# Reg.net
KiCad netlist of a schematic drawn in EAGLE
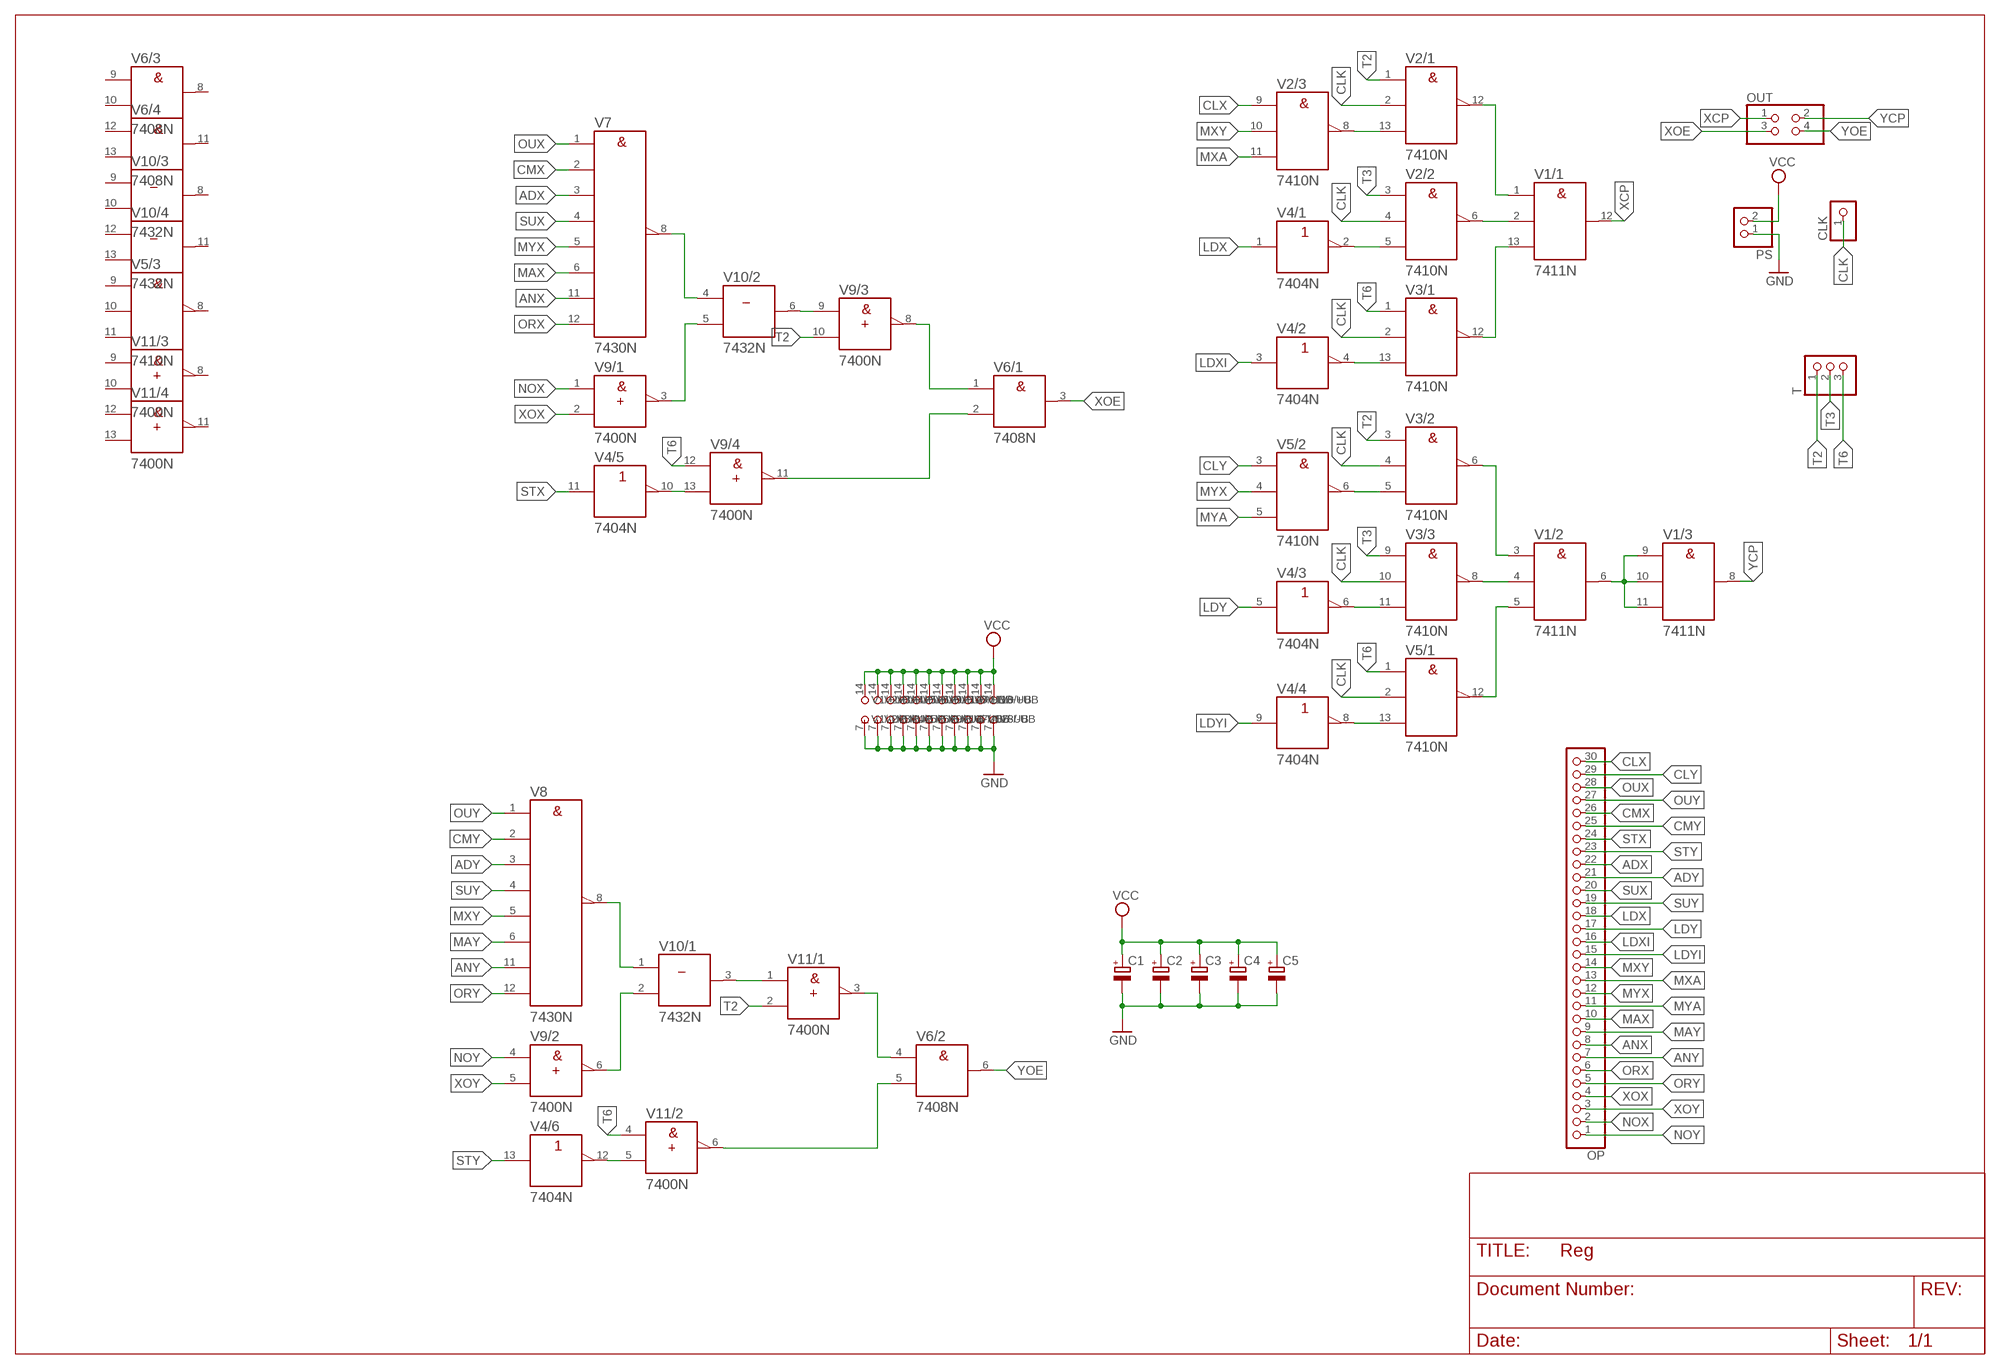
[diagram p0: schematic, sheet 1]

(export (version "E")
  (design (tool "Eeschema 10.0.6"))
  (components
    (comp (ref "C1")
      (value "CPOL-EUE2-5")
      (footprint "eagle-import:E2-5")
      (libsource (lib "eagle-import") (part "CPOL-EUE2-5"))
    )
    (comp (ref "C2")
      (value "CPOL-EUE2-5")
      (footprint "eagle-import:E2-5")
      (libsource (lib "eagle-import") (part "CPOL-EUE2-5"))
    )
    (comp (ref "C3")
      (value "CPOL-EUE2-5")
      (footprint "eagle-import:E2-5")
      (libsource (lib "eagle-import") (part "CPOL-EUE2-5"))
    )
    (comp (ref "C4")
      (value "CPOL-EUE2-5")
      (footprint "eagle-import:E2-5")
      (libsource (lib "eagle-import") (part "CPOL-EUE2-5"))
    )
    (comp (ref "C5")
      (value "CPOL-EUE2-5")
      (footprint "eagle-import:E2-5")
      (libsource (lib "eagle-import") (part "CPOL-EUE2-5"))
    )
    (comp (ref "CLK")
      (value "PINHD-1X1")
      (footprint "eagle-import:1X01")
      (libsource (lib "eagle-import") (part "PINHD-1X1"))
    )
    (comp (ref "OP")
      (value "PINHD-1X30")
      (footprint "eagle-import:1X30")
      (libsource (lib "eagle-import") (part "PINHD-1X30"))
    )
    (comp (ref "OUT")
      (value "PINHD-2X2")
      (footprint "eagle-import:2X02")
      (libsource (lib "eagle-import") (part "PINHD-2X2"))
    )
    (comp (ref "PS")
      (value "PINHD-1X2")
      (footprint "eagle-import:1X02")
      (libsource (lib "eagle-import") (part "PINHD-1X2"))
    )
    (comp (ref "T")
      (value "PINHD-1X3")
      (footprint "eagle-import:1X03")
      (libsource (lib "eagle-import") (part "PINHD-1X3"))
    )
    (comp (ref "V1")
      (value "7411N")
      (footprint "eagle-import:DIL14")
      (libsource (lib "eagle-import") (part "7411N"))
    )
    (comp (ref "V2")
      (value "7410N")
      (footprint "eagle-import:DIL14")
      (libsource (lib "eagle-import") (part "7410N"))
    )
    (comp (ref "V3")
      (value "7410N")
      (footprint "eagle-import:DIL14")
      (libsource (lib "eagle-import") (part "7410N"))
    )
    (comp (ref "V4")
      (value "7404N")
      (footprint "eagle-import:DIL14")
      (libsource (lib "eagle-import") (part "7404N"))
    )
    (comp (ref "V5")
      (value "7410N")
      (footprint "eagle-import:DIL14")
      (libsource (lib "eagle-import") (part "7410N"))
    )
    (comp (ref "V6")
      (value "7408N")
      (footprint "eagle-import:DIL14")
      (libsource (lib "eagle-import") (part "7408N"))
    )
    (comp (ref "V7")
      (value "7430N")
      (footprint "eagle-import:DIL14")
      (libsource (lib "eagle-import") (part "7430N"))
    )
    (comp (ref "V8")
      (value "7430N")
      (footprint "eagle-import:DIL14")
      (libsource (lib "eagle-import") (part "7430N"))
    )
    (comp (ref "V9")
      (value "7400N")
      (footprint "eagle-import:DIL14")
      (libsource (lib "eagle-import") (part "7400N"))
    )
    (comp (ref "V10")
      (value "7432N")
      (footprint "eagle-import:DIL14")
      (libsource (lib "eagle-import") (part "7432N"))
    )
    (comp (ref "V11")
      (value "7400N")
      (footprint "eagle-import:DIL14")
      (libsource (lib "eagle-import") (part "7400N"))
    )
  )
  (nets
    (net (code "1") (name "ADX") (class "Default")
      (node (ref "OP") (pin "22") (pinfunction "22_22") (pintype "passive"))
      (node (ref "V7") (pin "3") (pinfunction "C_3") (pintype "input"))
    )
    (net (code "2") (name "ADY") (class "Default")
      (node (ref "OP") (pin "21") (pinfunction "21_21") (pintype "passive"))
      (node (ref "V8") (pin "3") (pinfunction "C_3") (pintype "input"))
    )
    (net (code "3") (name "ANX") (class "Default")
      (node (ref "OP") (pin "8") (pinfunction "8_8") (pintype "passive"))
      (node (ref "V7") (pin "11") (pinfunction "G_11") (pintype "input"))
    )
    (net (code "4") (name "ANY") (class "Default")
      (node (ref "OP") (pin "7") (pinfunction "7_7") (pintype "passive"))
      (node (ref "V8") (pin "11") (pinfunction "G_11") (pintype "input"))
    )
    (net (code "5") (name "CLK") (class "Default")
      (node (ref "CLK") (pin "1") (pinfunction "1_1") (pintype "passive"))
      (node (ref "V2") (pin "2") (pinfunction "B_2") (pintype "input"))
      (node (ref "V2") (pin "4") (pinfunction "B_4") (pintype "input"))
      (node (ref "V3") (pin "10") (pinfunction "B_10") (pintype "input"))
      (node (ref "V3") (pin "2") (pinfunction "B_2") (pintype "input"))
      (node (ref "V3") (pin "4") (pinfunction "B_4") (pintype "input"))
      (node (ref "V5") (pin "2") (pinfunction "B_2") (pintype "input"))
    )
    (net (code "6") (name "CLX") (class "Default")
      (node (ref "OP") (pin "30") (pinfunction "30_30") (pintype "passive"))
      (node (ref "V2") (pin "9") (pinfunction "A_9") (pintype "input"))
    )
    (net (code "7") (name "CLY") (class "Default")
      (node (ref "OP") (pin "29") (pinfunction "29_29") (pintype "passive"))
      (node (ref "V5") (pin "3") (pinfunction "A_3") (pintype "input"))
    )
    (net (code "8") (name "CMX") (class "Default")
      (node (ref "OP") (pin "26") (pinfunction "26_26") (pintype "passive"))
      (node (ref "V7") (pin "2") (pinfunction "B_2") (pintype "input"))
    )
    (net (code "9") (name "CMY") (class "Default")
      (node (ref "OP") (pin "25") (pinfunction "25_25") (pintype "passive"))
      (node (ref "V8") (pin "2") (pinfunction "B_2") (pintype "input"))
    )
    (net (code "10") (name "GND") (class "Default")
      (node (ref "C1") (pin "-") (pinfunction "-_-") (pintype "passive"))
      (node (ref "C2") (pin "-") (pinfunction "-_-") (pintype "passive"))
      (node (ref "C3") (pin "-") (pinfunction "-_-") (pintype "passive"))
      (node (ref "C4") (pin "-") (pinfunction "-_-") (pintype "passive"))
      (node (ref "C5") (pin "-") (pinfunction "-_-") (pintype "passive"))
      (node (ref "PS") (pin "1") (pinfunction "1_1") (pintype "passive"))
      (node (ref "V1") (pin "7") (pinfunction "-UB_7") (pintype "power_in"))
      (node (ref "V10") (pin "7") (pinfunction "-UB_7") (pintype "power_in"))
      (node (ref "V11") (pin "7") (pinfunction "-UB_7") (pintype "power_in"))
      (node (ref "V2") (pin "7") (pinfunction "-UB_7") (pintype "power_in"))
      (node (ref "V3") (pin "7") (pinfunction "-UB_7") (pintype "power_in"))
      (node (ref "V4") (pin "7") (pinfunction "-UB_7") (pintype "power_in"))
      (node (ref "V5") (pin "7") (pinfunction "-UB_7") (pintype "power_in"))
      (node (ref "V6") (pin "7") (pinfunction "-UB_7") (pintype "power_in"))
      (node (ref "V7") (pin "7") (pinfunction "-UB_7") (pintype "power_in"))
      (node (ref "V8") (pin "7") (pinfunction "-UB_7") (pintype "power_in"))
      (node (ref "V9") (pin "7") (pinfunction "-UB_7") (pintype "power_in"))
    )
    (net (code "11") (name "LDX") (class "Default")
      (node (ref "OP") (pin "18") (pinfunction "18_18") (pintype "passive"))
      (node (ref "V4") (pin "1") (pinfunction "A_1") (pintype "input"))
    )
    (net (code "12") (name "LDXI") (class "Default")
      (node (ref "OP") (pin "16") (pinfunction "16_16") (pintype "passive"))
      (node (ref "V4") (pin "3") (pinfunction "A_3") (pintype "input"))
    )
    (net (code "13") (name "LDY") (class "Default")
      (node (ref "OP") (pin "17") (pinfunction "17_17") (pintype "passive"))
      (node (ref "V4") (pin "5") (pinfunction "A_5") (pintype "input"))
    )
    (net (code "14") (name "LDYI") (class "Default")
      (node (ref "OP") (pin "15") (pinfunction "15_15") (pintype "passive"))
      (node (ref "V4") (pin "9") (pinfunction "A_9") (pintype "input"))
    )
    (net (code "15") (name "MAX") (class "Default")
      (node (ref "OP") (pin "10") (pinfunction "10_10") (pintype "passive"))
      (node (ref "V7") (pin "6") (pinfunction "F_6") (pintype "input"))
    )
    (net (code "16") (name "MAY") (class "Default")
      (node (ref "OP") (pin "9") (pinfunction "9_9") (pintype "passive"))
      (node (ref "V8") (pin "6") (pinfunction "F_6") (pintype "input"))
    )
    (net (code "17") (name "MXA") (class "Default")
      (node (ref "OP") (pin "13") (pinfunction "13_13") (pintype "passive"))
      (node (ref "V2") (pin "11") (pinfunction "C_11") (pintype "input"))
    )
    (net (code "18") (name "MXY") (class "Default")
      (node (ref "OP") (pin "14") (pinfunction "14_14") (pintype "passive"))
      (node (ref "V2") (pin "10") (pinfunction "B_10") (pintype "input"))
      (node (ref "V8") (pin "5") (pinfunction "E_5") (pintype "input"))
    )
    (net (code "19") (name "MYA") (class "Default")
      (node (ref "OP") (pin "11") (pinfunction "11_11") (pintype "passive"))
      (node (ref "V5") (pin "5") (pinfunction "C_5") (pintype "input"))
    )
    (net (code "20") (name "MYX") (class "Default")
      (node (ref "OP") (pin "12") (pinfunction "12_12") (pintype "passive"))
      (node (ref "V5") (pin "4") (pinfunction "B_4") (pintype "input"))
      (node (ref "V7") (pin "5") (pinfunction "E_5") (pintype "input"))
    )
    (net (code "21") (name "NOX") (class "Default")
      (node (ref "OP") (pin "2") (pinfunction "2_2") (pintype "passive"))
      (node (ref "V9") (pin "1") (pinfunction "A_1") (pintype "input"))
    )
    (net (code "22") (name "NOY") (class "Default")
      (node (ref "OP") (pin "1") (pinfunction "1_1") (pintype "passive"))
      (node (ref "V9") (pin "4") (pinfunction "A_4") (pintype "input"))
    )
    (net (code "23") (name "Net-(V1C-A)") (class "Default")
      (node (ref "V1") (pin "1") (pinfunction "A_1") (pintype "input"))
      (node (ref "V2") (pin "12") (pinfunction "Y_12") (pintype "output"))
    )
    (net (code "24") (name "Net-(V1C-B)") (class "Default")
      (node (ref "V1") (pin "2") (pinfunction "B_2") (pintype "input"))
      (node (ref "V2") (pin "6") (pinfunction "Y_6") (pintype "output"))
    )
    (net (code "25") (name "Net-(V1C-C)") (class "Default")
      (node (ref "V1") (pin "13") (pinfunction "C_13") (pintype "input"))
      (node (ref "V3") (pin "12") (pinfunction "Y_12") (pintype "output"))
    )
    (net (code "26") (name "Net-(V1D-A)") (class "Default")
      (node (ref "V1") (pin "3") (pinfunction "A_3") (pintype "input"))
      (node (ref "V3") (pin "6") (pinfunction "Y_6") (pintype "output"))
    )
    (net (code "27") (name "Net-(V1D-B)") (class "Default")
      (node (ref "V1") (pin "4") (pinfunction "B_4") (pintype "input"))
      (node (ref "V3") (pin "8") (pinfunction "Y_8") (pintype "output"))
    )
    (net (code "28") (name "Net-(V1D-C)") (class "Default")
      (node (ref "V1") (pin "5") (pinfunction "C_5") (pintype "input"))
      (node (ref "V5") (pin "12") (pinfunction "Y_12") (pintype "output"))
    )
    (net (code "29") (name "Net-(V1D-Y)") (class "Default")
      (node (ref "V1") (pin "10") (pinfunction "B_10") (pintype "input"))
      (node (ref "V1") (pin "11") (pinfunction "C_11") (pintype "input"))
      (node (ref "V1") (pin "6") (pinfunction "Y_6") (pintype "output"))
      (node (ref "V1") (pin "9") (pinfunction "A_9") (pintype "input"))
    )
    (net (code "30") (name "Net-(V2C-C)") (class "Default")
      (node (ref "V2") (pin "13") (pinfunction "C_13") (pintype "input"))
      (node (ref "V2") (pin "8") (pinfunction "Y_8") (pintype "output"))
    )
    (net (code "31") (name "Net-(V2D-C)") (class "Default")
      (node (ref "V2") (pin "5") (pinfunction "C_5") (pintype "input"))
      (node (ref "V4") (pin "2") (pinfunction "Y_2") (pintype "output"))
    )
    (net (code "32") (name "Net-(V3C-C)") (class "Default")
      (node (ref "V3") (pin "13") (pinfunction "C_13") (pintype "input"))
      (node (ref "V4") (pin "4") (pinfunction "Y_4") (pintype "output"))
    )
    (net (code "33") (name "Net-(V3D-C)") (class "Default")
      (node (ref "V3") (pin "5") (pinfunction "C_5") (pintype "input"))
      (node (ref "V5") (pin "6") (pinfunction "Y_6") (pintype "output"))
    )
    (net (code "34") (name "Net-(V3E-C)") (class "Default")
      (node (ref "V3") (pin "11") (pinfunction "C_11") (pintype "input"))
      (node (ref "V4") (pin "6") (pinfunction "Y_6") (pintype "output"))
    )
    (net (code "35") (name "Net-(V4F-Y)") (class "Default")
      (node (ref "V4") (pin "8") (pinfunction "Y_8") (pintype "output"))
      (node (ref "V5") (pin "13") (pinfunction "C_13") (pintype "input"))
    )
    (net (code "36") (name "Net-(V4G-Y)") (class "Default")
      (node (ref "V4") (pin "10") (pinfunction "Y_10") (pintype "output"))
      (node (ref "V9") (pin "13") (pinfunction "B_13") (pintype "input"))
    )
    (net (code "37") (name "Net-(V6C-A)") (class "Default")
      (node (ref "V6") (pin "1") (pinfunction "A_1") (pintype "input"))
      (node (ref "V9") (pin "8") (pinfunction "Y_8") (pintype "output"))
    )
    (net (code "38") (name "Net-(V6C-B)") (class "Default")
      (node (ref "V6") (pin "2") (pinfunction "B_2") (pintype "input"))
      (node (ref "V9") (pin "11") (pinfunction "Y_11") (pintype "output"))
    )
    (net (code "39") (name "Net-(V10C-A)") (class "Default")
      (node (ref "V10") (pin "1") (pinfunction "A_1") (pintype "input"))
      (node (ref "V8") (pin "8") (pinfunction "Y_8") (pintype "output"))
    )
    (net (code "40") (name "Net-(V10C-B)") (class "Default")
      (node (ref "V10") (pin "2") (pinfunction "B_2") (pintype "input"))
      (node (ref "V9") (pin "6") (pinfunction "Y_6") (pintype "output"))
    )
    (net (code "41") (name "Net-(V10C-Y)") (class "Default")
      (node (ref "V10") (pin "3") (pinfunction "Y_3") (pintype "output"))
      (node (ref "V11") (pin "1") (pinfunction "A_1") (pintype "input"))
    )
    (net (code "42") (name "Net-(V10D-A)") (class "Default")
      (node (ref "V10") (pin "4") (pinfunction "A_4") (pintype "input"))
      (node (ref "V7") (pin "8") (pinfunction "Y_8") (pintype "output"))
    )
    (net (code "43") (name "Net-(V10D-B)") (class "Default")
      (node (ref "V10") (pin "5") (pinfunction "B_5") (pintype "input"))
      (node (ref "V9") (pin "3") (pinfunction "Y_3") (pintype "output"))
    )
    (net (code "44") (name "Net-(V10D-Y)") (class "Default")
      (node (ref "V10") (pin "6") (pinfunction "Y_6") (pintype "output"))
      (node (ref "V9") (pin "9") (pinfunction "A_9") (pintype "input"))
    )
    (net (code "45") (name "Net-(V11C-Y)") (class "Default")
      (node (ref "V11") (pin "3") (pinfunction "Y_3") (pintype "output"))
      (node (ref "V6") (pin "4") (pinfunction "A_4") (pintype "input"))
    )
    (net (code "46") (name "Net-(V11D-B)") (class "Default")
      (node (ref "V11") (pin "5") (pinfunction "B_5") (pintype "input"))
      (node (ref "V4") (pin "12") (pinfunction "Y_12") (pintype "output"))
    )
    (net (code "47") (name "Net-(V11D-Y)") (class "Default")
      (node (ref "V11") (pin "6") (pinfunction "Y_6") (pintype "output"))
      (node (ref "V6") (pin "5") (pinfunction "B_5") (pintype "input"))
    )
    (net (code "48") (name "ORX") (class "Default")
      (node (ref "OP") (pin "6") (pinfunction "6_6") (pintype "passive"))
      (node (ref "V7") (pin "12") (pinfunction "H_12") (pintype "input"))
    )
    (net (code "49") (name "ORY") (class "Default")
      (node (ref "OP") (pin "5") (pinfunction "5_5") (pintype "passive"))
      (node (ref "V8") (pin "12") (pinfunction "H_12") (pintype "input"))
    )
    (net (code "50") (name "OUX") (class "Default")
      (node (ref "OP") (pin "28") (pinfunction "28_28") (pintype "passive"))
      (node (ref "V7") (pin "1") (pinfunction "A_1") (pintype "input"))
    )
    (net (code "51") (name "OUY") (class "Default")
      (node (ref "OP") (pin "27") (pinfunction "27_27") (pintype "passive"))
      (node (ref "V8") (pin "1") (pinfunction "A_1") (pintype "input"))
    )
    (net (code "52") (name "STX") (class "Default")
      (node (ref "OP") (pin "24") (pinfunction "24_24") (pintype "passive"))
      (node (ref "V4") (pin "11") (pinfunction "A_11") (pintype "input"))
    )
    (net (code "53") (name "STY") (class "Default")
      (node (ref "OP") (pin "23") (pinfunction "23_23") (pintype "passive"))
      (node (ref "V4") (pin "13") (pinfunction "A_13") (pintype "input"))
    )
    (net (code "54") (name "SUX") (class "Default")
      (node (ref "OP") (pin "20") (pinfunction "20_20") (pintype "passive"))
      (node (ref "V7") (pin "4") (pinfunction "D_4") (pintype "input"))
    )
    (net (code "55") (name "SUY") (class "Default")
      (node (ref "OP") (pin "19") (pinfunction "19_19") (pintype "passive"))
      (node (ref "V8") (pin "4") (pinfunction "D_4") (pintype "input"))
    )
    (net (code "56") (name "T2") (class "Default")
      (node (ref "T") (pin "1") (pinfunction "1_1") (pintype "passive"))
      (node (ref "V11") (pin "2") (pinfunction "B_2") (pintype "input"))
      (node (ref "V2") (pin "1") (pinfunction "A_1") (pintype "input"))
      (node (ref "V3") (pin "3") (pinfunction "A_3") (pintype "input"))
      (node (ref "V9") (pin "10") (pinfunction "B_10") (pintype "input"))
    )
    (net (code "57") (name "T3") (class "Default")
      (node (ref "T") (pin "2") (pinfunction "2_2") (pintype "passive"))
      (node (ref "V2") (pin "3") (pinfunction "A_3") (pintype "input"))
      (node (ref "V3") (pin "9") (pinfunction "A_9") (pintype "input"))
    )
    (net (code "58") (name "T6") (class "Default")
      (node (ref "T") (pin "3") (pinfunction "3_3") (pintype "passive"))
      (node (ref "V11") (pin "4") (pinfunction "A_4") (pintype "input"))
      (node (ref "V3") (pin "1") (pinfunction "A_1") (pintype "input"))
      (node (ref "V5") (pin "1") (pinfunction "A_1") (pintype "input"))
      (node (ref "V9") (pin "12") (pinfunction "A_12") (pintype "input"))
    )
    (net (code "59") (name "VCC") (class "Default")
      (node (ref "C1") (pin "+") (pinfunction "+_+") (pintype "passive"))
      (node (ref "C2") (pin "+") (pinfunction "+_+") (pintype "passive"))
      (node (ref "C3") (pin "+") (pinfunction "+_+") (pintype "passive"))
      (node (ref "C4") (pin "+") (pinfunction "+_+") (pintype "passive"))
      (node (ref "C5") (pin "+") (pinfunction "+_+") (pintype "passive"))
      (node (ref "PS") (pin "2") (pinfunction "2_2") (pintype "passive"))
      (node (ref "V1") (pin "14") (pinfunction "+UB_14") (pintype "power_in"))
      (node (ref "V10") (pin "14") (pinfunction "+UB_14") (pintype "power_in"))
      (node (ref "V11") (pin "14") (pinfunction "+UB_14") (pintype "power_in"))
      (node (ref "V2") (pin "14") (pinfunction "+UB_14") (pintype "power_in"))
      (node (ref "V3") (pin "14") (pinfunction "+UB_14") (pintype "power_in"))
      (node (ref "V4") (pin "14") (pinfunction "+UB_14") (pintype "power_in"))
      (node (ref "V5") (pin "14") (pinfunction "+UB_14") (pintype "power_in"))
      (node (ref "V6") (pin "14") (pinfunction "+UB_14") (pintype "power_in"))
      (node (ref "V7") (pin "14") (pinfunction "+UB_14") (pintype "power_in"))
      (node (ref "V8") (pin "14") (pinfunction "+UB_14") (pintype "power_in"))
      (node (ref "V9") (pin "14") (pinfunction "+UB_14") (pintype "power_in"))
    )
    (net (code "60") (name "XCP") (class "Default")
      (node (ref "OUT") (pin "1") (pinfunction "1_1") (pintype "passive"))
      (node (ref "V1") (pin "12") (pinfunction "Y_12") (pintype "output"))
    )
    (net (code "61") (name "XOE") (class "Default")
      (node (ref "OUT") (pin "3") (pinfunction "3_3") (pintype "passive"))
      (node (ref "V6") (pin "3") (pinfunction "Y_3") (pintype "output"))
    )
    (net (code "62") (name "XOX") (class "Default")
      (node (ref "OP") (pin "4") (pinfunction "4_4") (pintype "passive"))
      (node (ref "V9") (pin "2") (pinfunction "B_2") (pintype "input"))
    )
    (net (code "63") (name "XOY") (class "Default")
      (node (ref "OP") (pin "3") (pinfunction "3_3") (pintype "passive"))
      (node (ref "V9") (pin "5") (pinfunction "B_5") (pintype "input"))
    )
    (net (code "64") (name "YCP") (class "Default")
      (node (ref "OUT") (pin "2") (pinfunction "2_2") (pintype "passive"))
      (node (ref "V1") (pin "8") (pinfunction "Y_8") (pintype "output"))
    )
    (net (code "65") (name "YOE") (class "Default")
      (node (ref "OUT") (pin "4") (pinfunction "4_4") (pintype "passive"))
      (node (ref "V6") (pin "6") (pinfunction "Y_6") (pintype "output"))
    )
    (net (code "66") (name "unconnected-(V5E-A-Pad9)") (class "Default")
      (node (ref "V5") (pin "9") (pinfunction "A_9") (pintype "input"))
    )
    (net (code "67") (name "unconnected-(V5E-B-Pad10)") (class "Default")
      (node (ref "V5") (pin "10") (pinfunction "B_10") (pintype "input"))
    )
    (net (code "68") (name "unconnected-(V5E-C-Pad11)") (class "Default")
      (node (ref "V5") (pin "11") (pinfunction "C_11") (pintype "input"))
    )
    (net (code "69") (name "unconnected-(V5E-Y-Pad8)") (class "Default")
      (node (ref "V5") (pin "8") (pinfunction "Y_8") (pintype "output"))
    )
    (net (code "70") (name "unconnected-(V6E-A-Pad9)") (class "Default")
      (node (ref "V6") (pin "9") (pinfunction "A_9") (pintype "input"))
    )
    (net (code "71") (name "unconnected-(V6E-B-Pad10)") (class "Default")
      (node (ref "V6") (pin "10") (pinfunction "B_10") (pintype "input"))
    )
    (net (code "72") (name "unconnected-(V6E-Y-Pad8)") (class "Default")
      (node (ref "V6") (pin "8") (pinfunction "Y_8") (pintype "output"))
    )
    (net (code "73") (name "unconnected-(V6F-A-Pad12)") (class "Default")
      (node (ref "V6") (pin "12") (pinfunction "A_12") (pintype "input"))
    )
    (net (code "74") (name "unconnected-(V6F-B-Pad13)") (class "Default")
      (node (ref "V6") (pin "13") (pinfunction "B_13") (pintype "input"))
    )
    (net (code "75") (name "unconnected-(V6F-Y-Pad11)") (class "Default")
      (node (ref "V6") (pin "11") (pinfunction "Y_11") (pintype "output"))
    )
    (net (code "76") (name "unconnected-(V10E-A-Pad9)") (class "Default")
      (node (ref "V10") (pin "9") (pinfunction "A_9") (pintype "input"))
    )
    (net (code "77") (name "unconnected-(V10E-B-Pad10)") (class "Default")
      (node (ref "V10") (pin "10") (pinfunction "B_10") (pintype "input"))
    )
    (net (code "78") (name "unconnected-(V10E-Y-Pad8)") (class "Default")
      (node (ref "V10") (pin "8") (pinfunction "Y_8") (pintype "output"))
    )
    (net (code "79") (name "unconnected-(V10F-A-Pad12)") (class "Default")
      (node (ref "V10") (pin "12") (pinfunction "A_12") (pintype "input"))
    )
    (net (code "80") (name "unconnected-(V10F-B-Pad13)") (class "Default")
      (node (ref "V10") (pin "13") (pinfunction "B_13") (pintype "input"))
    )
    (net (code "81") (name "unconnected-(V10F-Y-Pad11)") (class "Default")
      (node (ref "V10") (pin "11") (pinfunction "Y_11") (pintype "output"))
    )
    (net (code "82") (name "unconnected-(V11E-A-Pad9)") (class "Default")
      (node (ref "V11") (pin "9") (pinfunction "A_9") (pintype "input"))
    )
    (net (code "83") (name "unconnected-(V11E-B-Pad10)") (class "Default")
      (node (ref "V11") (pin "10") (pinfunction "B_10") (pintype "input"))
    )
    (net (code "84") (name "unconnected-(V11E-Y-Pad8)") (class "Default")
      (node (ref "V11") (pin "8") (pinfunction "Y_8") (pintype "output"))
    )
    (net (code "85") (name "unconnected-(V11F-A-Pad12)") (class "Default")
      (node (ref "V11") (pin "12") (pinfunction "A_12") (pintype "input"))
    )
    (net (code "86") (name "unconnected-(V11F-B-Pad13)") (class "Default")
      (node (ref "V11") (pin "13") (pinfunction "B_13") (pintype "input"))
    )
    (net (code "87") (name "unconnected-(V11F-Y-Pad11)") (class "Default")
      (node (ref "V11") (pin "11") (pinfunction "Y_11") (pintype "output"))
    )
  )
)
